# FMU_FMU3_REV_G.net
KiCad netlist of a schematic drawn in Altium Designer
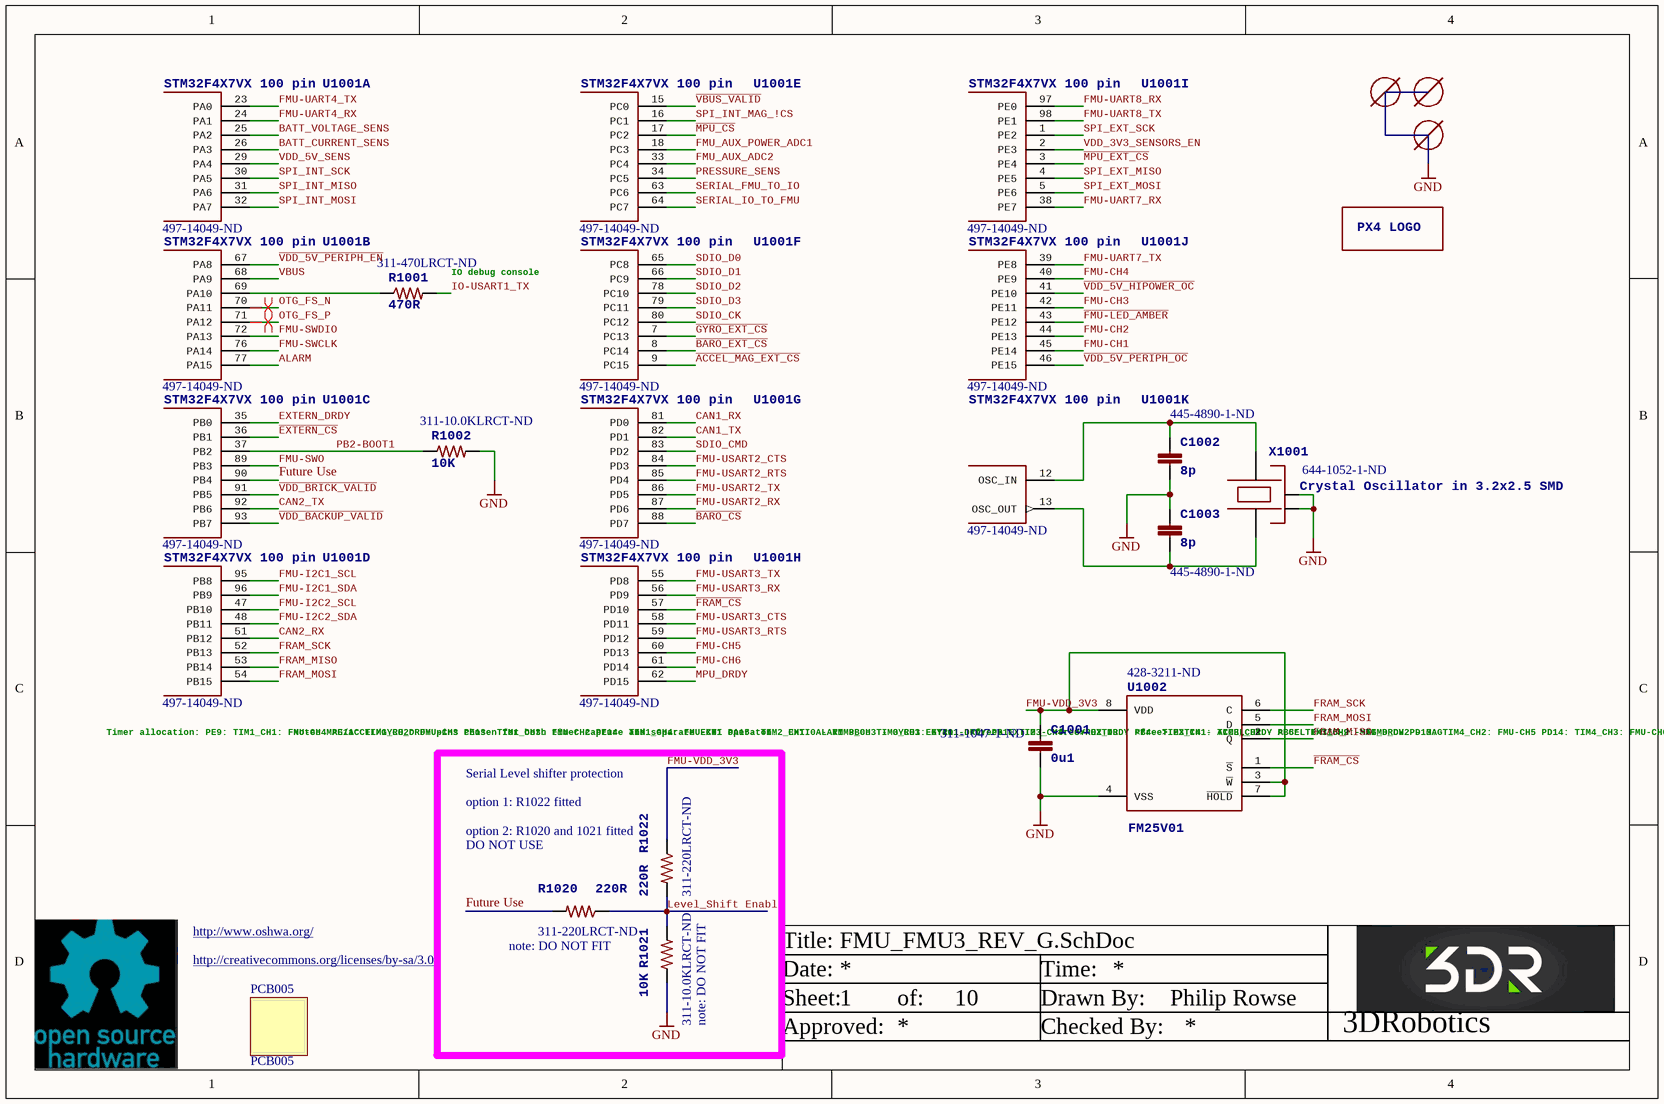
[diagram p0: FMU_FMU3_REV_G.SchDoc]

(export (version "E")
  (design (tool "Eeschema 10.0.6"))
  (components
    (comp (ref "C1001")
      (value "0u1")
      (footprint "0402-CAP")
      (description "CAP CER 0.1UF 16V Y5V 0402")
      (fields
        (field (name "PARTNO") "CC0402ZRY5V7BB104")
        (field (name "SUPPLIER PART NUMBER 1") "311-1047-1-ND")
        (field (name "3DR_PARTNO") "ECM0700")
      )
      (libsource (lib "pixhawk2") (part "CAP0402"))
    )
    (comp (ref "C1002")
      (value "8p")
      (footprint "0402-CAP")
      (description "CAP CER 8PF 50V C0G 0402")
      (fields
        (field (name "PARTNO") "C1005C0G1H080C")
        (field (name "SUPPLIER PART NUMBER 1") "445-4890-1-ND")
        (field (name "3DR_PARTNO") "ECM0710")
      )
      (libsource (lib "pixhawk2") (part "CAP0402"))
    )
    (comp (ref "C1003")
      (value "8p")
      (footprint "0402-CAP")
      (description "CAP CER 8PF 50V C0G 0402")
      (fields
        (field (name "PARTNO") "C1005C0G1H080C")
        (field (name "SUPPLIER PART NUMBER 1") "445-4890-1-ND")
        (field (name "3DR_PARTNO") "ECM0710")
      )
      (libsource (lib "pixhawk2") (part "CAP0402"))
    )
    (comp (ref "M3_MOUNT1001")
      (value "MOUNT-HOLE1.8MM")
      (footprint "MOUNT-HOLE1.8")
      (libsource (lib "pixhawk2") (part "MOUNT-HOLE1.8MM"))
    )
    (comp (ref "M3_MOUNT1003")
      (value "MOUNT-HOLE1.8MM")
      (footprint "MOUNT-HOLE1.8")
      (libsource (lib "pixhawk2") (part "MOUNT-HOLE1.8MM"))
    )
    (comp (ref "M3_MOUNT1004")
      (value "MOUNT-HOLE1.8MM")
      (footprint "MOUNT-HOLE1.8")
      (libsource (lib "pixhawk2") (part "MOUNT-HOLE1.8MM"))
    )
    (comp (ref "PCB005")
      (value "PCB005")
      (description "PCB,FMU, PX2, Board")
      (libsource (lib "lib_pixhawk") (part "PCB_0005"))
    )
    (comp (ref "R1001")
      (value "470R")
      (footprint "0402-RES")
      (description "RES 470 OHM 1/16W 1% 0402 SMD")
      (fields
        (field (name "PARTNO") "RC0402FR-07470RL")
        (field (name "SUPPLIER PART NUMBER 1") "311-470LRCT-ND")
        (field (name "3DR_PARTNO") "ECM0823")
      )
      (libsource (lib "pixhawk2") (part "RESISTOR0402-RES"))
    )
    (comp (ref "R1002")
      (value "10K")
      (footprint "0402-RES")
      (description "RES 10K OHM 1/16W 1% 0402 SMD")
      (fields
        (field (name "PARTNO") "RC0402FR-0710KL")
        (field (name "SUPPLIER PART NUMBER 1") "311-10.0KLRCT-ND")
        (field (name "3DR_PARTNO") "ECM0800")
      )
      (libsource (lib "pixhawk2") (part "RESISTOR0402-RES"))
    )
    (comp (ref "R1020")
      (value "220R")
      (footprint "0402-RES")
      (description "RES 220 OHM 1/16W 1% 0402 SMD")
      (fields
        (field (name "PARTNO") "RC0402FR-07220RL")
        (field (name "SUPPLIER PART NUMBER 1") "311-220LRCT-ND")
        (field (name "3DR_PARTNO") "ECM0821")
        (field (name "NOTE") "DO NOT FIT")
      )
      (libsource (lib "pixhawk2") (part "RESISTOR0402-RES"))
    )
    (comp (ref "R1021")
      (value "10K")
      (footprint "0402-RES")
      (description "RES 10K OHM 1/16W 1% 0402 SMD")
      (fields
        (field (name "PARTNO") "RC0402FR-0710KL")
        (field (name "SUPPLIER PART NUMBER 1") "311-10.0KLRCT-ND")
        (field (name "3DR_PARTNO") "ECM0800")
        (field (name "NOTE") "DO NOT FIT")
      )
      (libsource (lib "pixhawk2") (part "RESISTOR0402-RES"))
    )
    (comp (ref "R1022")
      (value "220R")
      (footprint "0402-RES")
      (description "RES 220 OHM 1/16W 1% 0402 SMD")
      (fields
        (field (name "PARTNO") "RC0402FR-07220RL")
        (field (name "SUPPLIER PART NUMBER 1") "311-220LRCT-ND")
        (field (name "3DR_PARTNO") "ECM0821")
      )
      (libsource (lib "pixhawk2") (part "RESISTOR0402-RES"))
    )
    (comp (ref "U$4")
      (value "PX4-LOGO-10MM")
      (footprint "PX4-LOGO-10MM")
      (fields (field (name "PX4 LOGO") "PX4 LOGO"))
      (libsource (lib "pixhawk2") (part "PX4-LOGO-10MM"))
    )
    (comp (ref "U1001")
      (value "STM32F4X7VX 100 pin")
      (footprint "TQFP100")
      (description "REV 3 Silicon or later IC MCU ARM 2MB FLASH 100LQFP")
      (fields (field (name "SUPPLIER PART NUMBER 1") "497-14049-ND") (field (name "3DR_PARTNO") "ECM0841"))
      (libsource (lib "pixhawk2") (part "STM32F4X7VX"))
    )
    (comp (ref "U1002")
      (value "FM25V01")
      (footprint "SO08")
      (description "IC FRAM 128KBIT 40MHZ 8SOIC")
      (fields
        (field (name "PARTNO") "FM25V01-G")
        (field (name "SUPPLIER PART NUMBER 1") "428-3211-ND")
        (field (name "3DR_PARTNO") "ECM0826")
      )
      (libsource (lib "pixhawk2") (part "FM25V01"))
    )
    (comp (ref "X1001")
      (value "Crystal Oscillator in 3.2x2.5 SMD")
      (footprint "OSCILLATOR-3.2X2.5")
      (description "CRYSTAL 24MHZ 8PF SMD")
      (fields
        (field (name "SUPPLIER PART NUMBER 1") "644-1052-1-ND")
        (field (name "3DR_PARTNO") "ECM0708")
        (field (name "PARTNO") "NX3225SA-24.000MHZ-STD-CSR-1")
      )
      (libsource (lib "pixhawk2") (part "OSCILLATOR-3.2X2.5"))
    )
  )
  (nets
    (net (code "1") (name "/ALARM") (class "Default")
      (node (ref "U1001") (pin "77") (pinfunction "PA15_77") (pintype "passive"))
    )
    (net (code "2") (name "/BATT_CURRENT_SENS") (class "Default")
      (node (ref "U1001") (pin "26") (pinfunction "PA3_26") (pintype "passive"))
    )
    (net (code "3") (name "/BATT_VOLTAGE_SENS") (class "Default")
      (node (ref "U1001") (pin "25") (pinfunction "PA2_25") (pintype "passive"))
    )
    (net (code "4") (name "/CAN1_RX") (class "Default")
      (node (ref "U1001") (pin "81") (pinfunction "PD0_81") (pintype "passive"))
    )
    (net (code "5") (name "/CAN1_TX") (class "Default")
      (node (ref "U1001") (pin "82") (pinfunction "PD1_82") (pintype "passive"))
    )
    (net (code "6") (name "/CAN2_RX") (class "Default")
      (node (ref "U1001") (pin "51") (pinfunction "PB12_51") (pintype "passive"))
    )
    (net (code "7") (name "/CAN2_TX") (class "Default")
      (node (ref "U1001") (pin "92") (pinfunction "PB6_92") (pintype "passive"))
    )
    (net (code "8") (name "/EXTERN_DRDY") (class "Default")
      (node (ref "U1001") (pin "35") (pinfunction "PB0_35") (pintype "passive"))
    )
    (net (code "9") (name "/FMU-CH1") (class "Default")
      (node (ref "U1001") (pin "45") (pinfunction "PE14_45") (pintype "passive"))
    )
    (net (code "10") (name "/FMU-CH2") (class "Default")
      (node (ref "U1001") (pin "44") (pinfunction "PE13_44") (pintype "passive"))
    )
    (net (code "11") (name "/FMU-CH3") (class "Default")
      (node (ref "U1001") (pin "42") (pinfunction "PE11_42") (pintype "passive"))
    )
    (net (code "12") (name "/FMU-CH4") (class "Default")
      (node (ref "U1001") (pin "40") (pinfunction "PE9_40") (pintype "passive"))
    )
    (net (code "13") (name "/FMU-CH5") (class "Default")
      (node (ref "U1001") (pin "60") (pinfunction "PD13_60") (pintype "passive"))
    )
    (net (code "14") (name "/FMU-CH6") (class "Default")
      (node (ref "U1001") (pin "61") (pinfunction "PD14_61") (pintype "passive"))
    )
    (net (code "15") (name "/FMU-I2C1_SCL") (class "Default")
      (node (ref "U1001") (pin "95") (pinfunction "PB8_95") (pintype "passive"))
    )
    (net (code "16") (name "/FMU-I2C1_SDA") (class "Default")
      (node (ref "U1001") (pin "96") (pinfunction "PB9_96") (pintype "passive"))
    )
    (net (code "17") (name "/FMU-I2C2_SCL") (class "Default")
      (node (ref "U1001") (pin "47") (pinfunction "PB10_47") (pintype "passive"))
    )
    (net (code "18") (name "/FMU-I2C2_SDA") (class "Default")
      (node (ref "U1001") (pin "48") (pinfunction "PB11_48") (pintype "passive"))
    )
    (net (code "19") (name "/FMU-SWCLK") (class "Default")
      (node (ref "U1001") (pin "76") (pinfunction "PA14_76") (pintype "passive"))
    )
    (net (code "20") (name "/FMU-SWDIO") (class "Default")
      (node (ref "U1001") (pin "72") (pinfunction "PA13_72") (pintype "passive"))
    )
    (net (code "21") (name "/FMU-SWO") (class "Default")
      (node (ref "U1001") (pin "89") (pinfunction "PB3_89") (pintype "passive"))
    )
    (net (code "22") (name "/FMU-UART4_RX") (class "Default")
      (node (ref "U1001") (pin "24") (pinfunction "PA1_24") (pintype "passive"))
    )
    (net (code "23") (name "/FMU-UART4_TX") (class "Default")
      (node (ref "U1001") (pin "23") (pinfunction "PA0_23") (pintype "passive"))
    )
    (net (code "24") (name "/FMU-UART7_RX") (class "Default")
      (node (ref "U1001") (pin "38") (pinfunction "PE7_38") (pintype "passive"))
    )
    (net (code "25") (name "/FMU-UART7_TX") (class "Default")
      (node (ref "U1001") (pin "39") (pinfunction "PE8_39") (pintype "passive"))
    )
    (net (code "26") (name "/FMU-UART8_RX") (class "Default")
      (node (ref "U1001") (pin "97") (pinfunction "PE0_97") (pintype "passive"))
    )
    (net (code "27") (name "/FMU-UART8_TX") (class "Default")
      (node (ref "U1001") (pin "98") (pinfunction "PE1_98") (pintype "passive"))
    )
    (net (code "28") (name "/FMU-USART2_CTS") (class "Default")
      (node (ref "U1001") (pin "84") (pinfunction "PD3_84") (pintype "passive"))
    )
    (net (code "29") (name "/FMU-USART2_RTS") (class "Default")
      (node (ref "U1001") (pin "85") (pinfunction "PD4_85") (pintype "passive"))
    )
    (net (code "30") (name "/FMU-USART2_RX") (class "Default")
      (node (ref "U1001") (pin "87") (pinfunction "PD6_87") (pintype "passive"))
    )
    (net (code "31") (name "/FMU-USART2_TX") (class "Default")
      (node (ref "U1001") (pin "86") (pinfunction "PD5_86") (pintype "passive"))
    )
    (net (code "32") (name "/FMU-USART3_CTS") (class "Default")
      (node (ref "U1001") (pin "58") (pinfunction "PD11_58") (pintype "passive"))
    )
    (net (code "33") (name "/FMU-USART3_RTS") (class "Default")
      (node (ref "U1001") (pin "59") (pinfunction "PD12_59") (pintype "passive"))
    )
    (net (code "34") (name "/FMU-USART3_RX") (class "Default")
      (node (ref "U1001") (pin "56") (pinfunction "PD9_56") (pintype "passive"))
    )
    (net (code "35") (name "/FMU-USART3_TX") (class "Default")
      (node (ref "U1001") (pin "55") (pinfunction "PD8_55") (pintype "passive"))
    )
    (net (code "36") (name "/FMU-VDD_3V3") (class "Default")
      (node (ref "C1001") (pin "P$1") (pinfunction "1_P$1") (pintype "passive"))
      (node (ref "R1022") (pin "P$1") (pinfunction "1_P$1") (pintype "passive"))
      (node (ref "U1002") (pin "3") (pinfunction "~{W}_3") (pintype "passive"))
      (node (ref "U1002") (pin "7") (pinfunction "~{HOLD}_7") (pintype "passive"))
      (node (ref "U1002") (pin "8") (pinfunction "VDD_8") (pintype "passive"))
    )
    (net (code "37") (name "/FMU_AUX_ADC2") (class "Default")
      (node (ref "U1001") (pin "33") (pinfunction "PC4_33") (pintype "passive"))
    )
    (net (code "38") (name "/FMU_AUX_POWER_ADC1") (class "Default")
      (node (ref "U1001") (pin "18") (pinfunction "PC3_18") (pintype "passive"))
    )
    (net (code "39") (name "/FRAM_MISO") (class "Default")
      (node (ref "U1001") (pin "53") (pinfunction "PB14_53") (pintype "passive"))
      (node (ref "U1002") (pin "2") (pinfunction "Q_2") (pintype "passive"))
    )
    (net (code "40") (name "/FRAM_MOSI") (class "Default")
      (node (ref "U1001") (pin "54") (pinfunction "PB15_54") (pintype "passive"))
      (node (ref "U1002") (pin "5") (pinfunction "D_5") (pintype "passive"))
    )
    (net (code "41") (name "/FRAM_SCK") (class "Default")
      (node (ref "U1001") (pin "52") (pinfunction "PB13_52") (pintype "passive"))
      (node (ref "U1002") (pin "6") (pinfunction "C_6") (pintype "passive"))
    )
    (net (code "42") (name "/Future Use") (class "Default")
      (node (ref "R1020") (pin "P$2") (pinfunction "2_P$2") (pintype "passive"))
      (node (ref "U1001") (pin "90") (pinfunction "PB4_90") (pintype "passive"))
    )
    (net (code "43") (name "/IO-USART1_TX") (class "Default")
      (node (ref "R1001") (pin "P$2") (pinfunction "2_P$2") (pintype "passive"))
    )
    (net (code "44") (name "/Level_Shift Enable") (class "Default")
      (node (ref "R1020") (pin "P$1") (pinfunction "1_P$1") (pintype "passive"))
      (node (ref "R1021") (pin "P$2") (pinfunction "2_P$2") (pintype "passive"))
      (node (ref "R1022") (pin "P$2") (pinfunction "2_P$2") (pintype "passive"))
    )
    (net (code "45") (name "/MPU_DRDY") (class "Default")
      (node (ref "U1001") (pin "62") (pinfunction "PD15_62") (pintype "passive"))
    )
    (net (code "46") (name "/OTG_FS_N") (class "Default")
      (node (ref "U1001") (pin "70") (pinfunction "PA11_70") (pintype "passive"))
    )
    (net (code "47") (name "/OTG_FS_P") (class "Default")
      (node (ref "U1001") (pin "71") (pinfunction "PA12_71") (pintype "passive"))
    )
    (net (code "48") (name "/PB2-BOOT1") (class "Default")
      (node (ref "R1002") (pin "P$1") (pinfunction "1_P$1") (pintype "passive"))
      (node (ref "U1001") (pin "37") (pinfunction "PB2_37") (pintype "passive"))
    )
    (net (code "49") (name "/PRESSURE_SENS") (class "Default")
      (node (ref "U1001") (pin "34") (pinfunction "PC5_34") (pintype "passive"))
    )
    (net (code "50") (name "/SDIO_CK") (class "Default")
      (node (ref "U1001") (pin "80") (pinfunction "PC12_80") (pintype "passive"))
    )
    (net (code "51") (name "/SDIO_CMD") (class "Default")
      (node (ref "U1001") (pin "83") (pinfunction "PD2_83") (pintype "passive"))
    )
    (net (code "52") (name "/SDIO_D0") (class "Default")
      (node (ref "U1001") (pin "65") (pinfunction "PC8_65") (pintype "passive"))
    )
    (net (code "53") (name "/SDIO_D1") (class "Default")
      (node (ref "U1001") (pin "66") (pinfunction "PC9_66") (pintype "passive"))
    )
    (net (code "54") (name "/SDIO_D2") (class "Default")
      (node (ref "U1001") (pin "78") (pinfunction "PC10_78") (pintype "passive"))
    )
    (net (code "55") (name "/SDIO_D3") (class "Default")
      (node (ref "U1001") (pin "79") (pinfunction "PC11_79") (pintype "passive"))
    )
    (net (code "56") (name "/SERIAL_FMU_TO_IO") (class "Default")
      (node (ref "U1001") (pin "63") (pinfunction "PC6_63") (pintype "passive"))
    )
    (net (code "57") (name "/SERIAL_IO_TO_FMU") (class "Default")
      (node (ref "U1001") (pin "64") (pinfunction "PC7_64") (pintype "passive"))
    )
    (net (code "58") (name "/SPI_EXT_MISO") (class "Default")
      (node (ref "U1001") (pin "4") (pinfunction "PE5_4") (pintype "passive"))
    )
    (net (code "59") (name "/SPI_EXT_MOSI") (class "Default")
      (node (ref "U1001") (pin "5") (pinfunction "PE6_5") (pintype "passive"))
    )
    (net (code "60") (name "/SPI_EXT_SCK") (class "Default")
      (node (ref "U1001") (pin "1") (pinfunction "PE2_1") (pintype "passive"))
    )
    (net (code "61") (name "/SPI_INT_MAG_!CS") (class "Default")
      (node (ref "U1001") (pin "16") (pinfunction "PC1_16") (pintype "passive"))
    )
    (net (code "62") (name "/SPI_INT_MISO") (class "Default")
      (node (ref "U1001") (pin "31") (pinfunction "PA6_31") (pintype "passive"))
    )
    (net (code "63") (name "/SPI_INT_MOSI") (class "Default")
      (node (ref "U1001") (pin "32") (pinfunction "PA7_32") (pintype "passive"))
    )
    (net (code "64") (name "/SPI_INT_SCK") (class "Default")
      (node (ref "U1001") (pin "30") (pinfunction "PA5_30") (pintype "passive"))
    )
    (net (code "65") (name "/VBUS") (class "Default")
      (node (ref "U1001") (pin "68") (pinfunction "PA9_68") (pintype "passive"))
    )
    (net (code "66") (name "/VDD_3V3_SENSORS_EN") (class "Default")
      (node (ref "U1001") (pin "2") (pinfunction "PE3_2") (pintype "passive"))
    )
    (net (code "67") (name "/VDD_5V_SENS") (class "Default")
      (node (ref "U1001") (pin "29") (pinfunction "PA4_29") (pintype "passive"))
    )
    (net (code "68") (name "/~{ACCEL_MAG_EXT_CS}") (class "Default")
      (node (ref "U1001") (pin "9") (pinfunction "PC15_9") (pintype "passive"))
    )
    (net (code "69") (name "/~{BARO_CS}") (class "Default")
      (node (ref "U1001") (pin "88") (pinfunction "PD7_88") (pintype "passive"))
    )
    (net (code "70") (name "/~{BARO_EXT_CS}") (class "Default")
      (node (ref "U1001") (pin "8") (pinfunction "PC14_8") (pintype "passive"))
    )
    (net (code "71") (name "/~{EXTERN_CS}") (class "Default")
      (node (ref "U1001") (pin "36") (pinfunction "PB1_36") (pintype "passive"))
    )
    (net (code "72") (name "/~{FMU-LED_AMBER}") (class "Default")
      (node (ref "U1001") (pin "43") (pinfunction "PE12_43") (pintype "passive"))
    )
    (net (code "73") (name "/~{FRAM_CS}") (class "Default")
      (node (ref "U1001") (pin "57") (pinfunction "PD10_57") (pintype "passive"))
      (node (ref "U1002") (pin "1") (pinfunction "~{S}_1") (pintype "passive"))
    )
    (net (code "74") (name "/~{GYRO_EXT_CS}") (class "Default")
      (node (ref "U1001") (pin "7") (pinfunction "PC13_7") (pintype "passive"))
    )
    (net (code "75") (name "/~{MPU_CS}") (class "Default")
      (node (ref "U1001") (pin "17") (pinfunction "PC2_17") (pintype "passive"))
    )
    (net (code "76") (name "/~{MPU_EXT_CS}") (class "Default")
      (node (ref "U1001") (pin "3") (pinfunction "PE4_3") (pintype "passive"))
    )
    (net (code "77") (name "/~{VBUS_VALID}") (class "Default")
      (node (ref "U1001") (pin "15") (pinfunction "PC0_15") (pintype "passive"))
    )
    (net (code "78") (name "/~{VDD_5V_HIPOWER_OC}") (class "Default")
      (node (ref "U1001") (pin "41") (pinfunction "PE10_41") (pintype "passive"))
    )
    (net (code "79") (name "/~{VDD_5V_PERIPH_EN}") (class "Default")
      (node (ref "U1001") (pin "67") (pinfunction "PA8_67") (pintype "passive"))
    )
    (net (code "80") (name "/~{VDD_5V_PERIPH_OC}") (class "Default")
      (node (ref "U1001") (pin "46") (pinfunction "PE15_46") (pintype "passive"))
    )
    (net (code "81") (name "/~{VDD_BACKUP_VALID}") (class "Default")
      (node (ref "U1001") (pin "93") (pinfunction "PB7_93") (pintype "passive"))
    )
    (net (code "82") (name "/~{VDD_BRICK_VALID}") (class "Default")
      (node (ref "U1001") (pin "91") (pinfunction "PB5_91") (pintype "passive"))
    )
    (net (code "83") (name "GND") (class "Default")
      (node (ref "C1001") (pin "P$2") (pinfunction "2_P$2") (pintype "passive"))
      (node (ref "C1002") (pin "P$2") (pinfunction "2_P$2") (pintype "passive"))
      (node (ref "C1003") (pin "P$1") (pinfunction "1_P$1") (pintype "passive"))
      (node (ref "R1002") (pin "P$2") (pinfunction "2_P$2") (pintype "passive"))
      (node (ref "R1021") (pin "P$1") (pinfunction "1_P$1") (pintype "passive"))
      (node (ref "U1002") (pin "4") (pinfunction "VSS_4") (pintype "passive"))
      (node (ref "X1001") (pin "2") (pinfunction "NC_2_2") (pintype "open_emitter"))
      (node (ref "X1001") (pin "4") (pinfunction "NC_4_4") (pintype "open_emitter"))
    )
    (net (code "84") (name "Net-(C1002-1)") (class "Default")
      (node (ref "C1002") (pin "P$1") (pinfunction "1_P$1") (pintype "passive"))
      (node (ref "U1001") (pin "12") (pinfunction "OSC_IN_12") (pintype "passive"))
      (node (ref "X1001") (pin "3") (pinfunction "3_3") (pintype "passive"))
    )
    (net (code "85") (name "Net-(C1003-2)") (class "Default")
      (node (ref "C1003") (pin "P$2") (pinfunction "2_P$2") (pintype "passive"))
      (node (ref "U1001") (pin "13") (pinfunction "OSC_OUT_13") (pintype "output"))
      (node (ref "X1001") (pin "1") (pinfunction "1_1") (pintype "passive"))
    )
    (net (code "86") (name "Net-(R1001-1)") (class "Default")
      (node (ref "R1001") (pin "P$1") (pinfunction "1_P$1") (pintype "passive"))
      (node (ref "U1001") (pin "69") (pinfunction "PA10_69") (pintype "passive"))
    )
  )
)
